# CTR_MCU_Power.net
KiCad netlist of a schematic drawn in Altium Designer
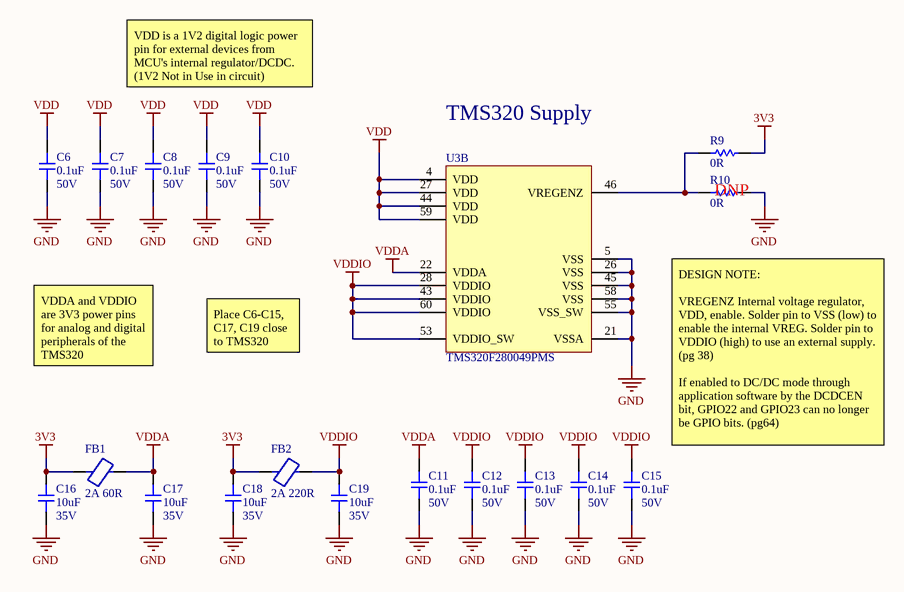
[diagram p0: CTR_MCU_Power.SchDoc]

(export (version "E")
  (design (tool "Eeschema 10.0.6"))
  (components
    (comp (ref "C6")
      (value "0603-0.1uF-50V")
      (footprint "CAP-0603")
      (description "CAP CER 0.1UF 50V X7R 0603")
      (fields
        (field (name "MANUFACTURER") "Kyocera AVX")
        (field (name "MANUFACTURER PART NUMBER") "06035C104JAT4A")
        (field (name "CAPACITANCE") "0.1uF")
        (field (name "VOLTAGE RATING") "50V")
      )
      (libsource (lib "InverterSCHLib") (part "0603-0.1uF-50V"))
    )
    (comp (ref "C7")
      (value "0603-0.1uF-50V")
      (footprint "CAP-0603")
      (description "CAP CER 0.1UF 50V X7R 0603")
      (fields
        (field (name "MANUFACTURER") "Kyocera AVX")
        (field (name "MANUFACTURER PART NUMBER") "06035C104JAT4A")
        (field (name "CAPACITANCE") "0.1uF")
        (field (name "VOLTAGE RATING") "50V")
      )
      (libsource (lib "InverterSCHLib") (part "0603-0.1uF-50V"))
    )
    (comp (ref "C8")
      (value "0603-0.1uF-50V")
      (footprint "CAP-0603")
      (description "CAP CER 0.1UF 50V X7R 0603")
      (fields
        (field (name "MANUFACTURER") "Kyocera AVX")
        (field (name "MANUFACTURER PART NUMBER") "06035C104JAT4A")
        (field (name "CAPACITANCE") "0.1uF")
        (field (name "VOLTAGE RATING") "50V")
      )
      (libsource (lib "InverterSCHLib") (part "0603-0.1uF-50V"))
    )
    (comp (ref "C9")
      (value "0603-0.1uF-50V")
      (footprint "CAP-0603")
      (description "CAP CER 0.1UF 50V X7R 0603")
      (fields
        (field (name "MANUFACTURER") "Kyocera AVX")
        (field (name "MANUFACTURER PART NUMBER") "06035C104JAT4A")
        (field (name "CAPACITANCE") "0.1uF")
        (field (name "VOLTAGE RATING") "50V")
      )
      (libsource (lib "InverterSCHLib") (part "0603-0.1uF-50V"))
    )
    (comp (ref "C10")
      (value "0603-0.1uF-50V")
      (footprint "CAP-0603")
      (description "CAP CER 0.1UF 50V X7R 0603")
      (fields
        (field (name "MANUFACTURER") "Kyocera AVX")
        (field (name "MANUFACTURER PART NUMBER") "06035C104JAT4A")
        (field (name "CAPACITANCE") "0.1uF")
        (field (name "VOLTAGE RATING") "50V")
      )
      (libsource (lib "InverterSCHLib") (part "0603-0.1uF-50V"))
    )
    (comp (ref "C11")
      (value "0603-0.1uF-50V")
      (footprint "CAP-0603")
      (description "CAP CER 0.1UF 50V X7R 0603")
      (fields
        (field (name "MANUFACTURER") "Kyocera AVX")
        (field (name "MANUFACTURER PART NUMBER") "06035C104JAT4A")
        (field (name "CAPACITANCE") "0.1uF")
        (field (name "VOLTAGE RATING") "50V")
      )
      (libsource (lib "InverterSCHLib") (part "0603-0.1uF-50V"))
    )
    (comp (ref "C12")
      (value "0603-0.1uF-50V")
      (footprint "CAP-0603")
      (description "CAP CER 0.1UF 50V X7R 0603")
      (fields
        (field (name "MANUFACTURER") "Kyocera AVX")
        (field (name "MANUFACTURER PART NUMBER") "06035C104JAT4A")
        (field (name "CAPACITANCE") "0.1uF")
        (field (name "VOLTAGE RATING") "50V")
      )
      (libsource (lib "InverterSCHLib") (part "0603-0.1uF-50V"))
    )
    (comp (ref "C13")
      (value "0603-0.1uF-50V")
      (footprint "CAP-0603")
      (description "CAP CER 0.1UF 50V X7R 0603")
      (fields
        (field (name "MANUFACTURER") "Kyocera AVX")
        (field (name "MANUFACTURER PART NUMBER") "06035C104JAT4A")
        (field (name "CAPACITANCE") "0.1uF")
        (field (name "VOLTAGE RATING") "50V")
      )
      (libsource (lib "InverterSCHLib") (part "0603-0.1uF-50V"))
    )
    (comp (ref "C14")
      (value "0603-0.1uF-50V")
      (footprint "CAP-0603")
      (description "CAP CER 0.1UF 50V X7R 0603")
      (fields
        (field (name "MANUFACTURER") "Kyocera AVX")
        (field (name "MANUFACTURER PART NUMBER") "06035C104JAT4A")
        (field (name "CAPACITANCE") "0.1uF")
        (field (name "VOLTAGE RATING") "50V")
      )
      (libsource (lib "InverterSCHLib") (part "0603-0.1uF-50V"))
    )
    (comp (ref "C15")
      (value "0603-0.1uF-50V")
      (footprint "CAP-0603")
      (description "CAP CER 0.1UF 50V X7R 0603")
      (fields
        (field (name "MANUFACTURER") "Kyocera AVX")
        (field (name "MANUFACTURER PART NUMBER") "06035C104JAT4A")
        (field (name "CAPACITANCE") "0.1uF")
        (field (name "VOLTAGE RATING") "50V")
      )
      (libsource (lib "InverterSCHLib") (part "0603-0.1uF-50V"))
    )
    (comp (ref "C16")
      (value "0603-10uF-35V")
      (footprint "CAP-0603")
      (description "CAP CER 10UF 35V X5R 0603")
      (fields
        (field (name "MANUFACTURER") "Murata")
        (field (name "MANUFACTURER PART NUMBER") "GRM188R6YA106MA73D")
        (field (name "CAPACITANCE") "10uF")
        (field (name "VOLTAGE RATING") "35V")
      )
      (libsource (lib "InverterSCHLib") (part "0603-10uF-35V"))
    )
    (comp (ref "C17")
      (value "0603-10uF-35V")
      (footprint "CAP-0603")
      (description "CAP CER 10UF 35V X5R 0603")
      (fields
        (field (name "MANUFACTURER") "Murata")
        (field (name "MANUFACTURER PART NUMBER") "GRM188R6YA106MA73D")
        (field (name "CAPACITANCE") "10uF")
        (field (name "VOLTAGE RATING") "35V")
      )
      (libsource (lib "InverterSCHLib") (part "0603-10uF-35V"))
    )
    (comp (ref "C18")
      (value "0603-10uF-35V")
      (footprint "CAP-0603")
      (description "CAP CER 10UF 35V X5R 0603")
      (fields
        (field (name "MANUFACTURER") "Murata")
        (field (name "MANUFACTURER PART NUMBER") "GRM188R6YA106MA73D")
        (field (name "CAPACITANCE") "10uF")
        (field (name "VOLTAGE RATING") "35V")
      )
      (libsource (lib "InverterSCHLib") (part "0603-10uF-35V"))
    )
    (comp (ref "C19")
      (value "0603-10uF-35V")
      (footprint "CAP-0603")
      (description "CAP CER 10UF 35V X5R 0603")
      (fields
        (field (name "MANUFACTURER") "Murata")
        (field (name "MANUFACTURER PART NUMBER") "GRM188R6YA106MA73D")
        (field (name "CAPACITANCE") "10uF")
        (field (name "VOLTAGE RATING") "35V")
      )
      (libsource (lib "InverterSCHLib") (part "0603-10uF-35V"))
    )
    (comp (ref "FB1")
      (value "2A 60R")
      (footprint "FB-0805")
      (description "FERRITE BEAD 60 OHM 0805 1LN")
      (fields
        (field (name "MANUFACTURER") "Taiyo Yuden")
        (field (name "MANUFACTURER PART NUMBER") "BKP2125HS600-T")
      )
      (libsource (lib "InverterSCHLib") (part "BKP2125HS600-T"))
    )
    (comp (ref "FB2")
      (value "2A 220R")
      (footprint "FB-0805")
      (description "FERRITE BEAD 220 OHM 0805 1LN")
      (fields
        (field (name "MANUFACTURER") "Murata")
        (field (name "MANUFACTURER PART NUMBER") "BLM21PG221SN1D")
      )
      (libsource (lib "InverterSCHLib") (part "BLM21PG221SN1D"))
    )
    (comp (ref "R9")
      (value "0R")
      (footprint "RES-0603")
      (description "RES SMD 0 OHM JUMPER 1/10W 0603")
      (fields
        (field (name "MANUFACTURER") "Yageo")
        (field (name "MANUFACTURER PART NUMBER") "RC0603JR-070RL")
      )
      (libsource (lib "InverterSCHLib") (part "0603-0R"))
    )
    (comp (ref "R10")
      (value "0R")
      (footprint "RES-0603")
      (description "RES SMD 0 OHM JUMPER 1/10W 0603")
      (fields
        (field (name "MANUFACTURER") "Yageo")
        (field (name "MANUFACTURER PART NUMBER") "RC0603JR-070RL")
      )
      (libsource (lib "InverterSCHLib") (part "0603-0R"))
    )
    (comp (ref "U3")
      (value "TMS320F280049PMS")
      (footprint "64QFP")
      (description "IC MCU 32BIT 256KB FLASH 64LQFP")
      (fields
        (field (name "MANUFACTURER") "Texas Instruments")
        (field (name "MANUFACTURER PART NUMBER") "F280049CPMS")
      )
      (libsource (lib "InverterSCHLib") (part "TMS320F280049"))
    )
  )
  (nets
    (net (code "1") (name "3V3") (class "Default")
      (node (ref "C16") (pin "2") (pinfunction "2_2") (pintype "passive"))
      (node (ref "C18") (pin "2") (pinfunction "2_2") (pintype "passive"))
      (node (ref "FB1") (pin "1") (pinfunction "1_1") (pintype "passive"))
      (node (ref "FB2") (pin "1") (pinfunction "1_1") (pintype "passive"))
      (node (ref "R9") (pin "2") (pinfunction "2_2") (pintype "passive"))
    )
    (net (code "2") (name "GND") (class "Default")
      (node (ref "C10") (pin "1") (pinfunction "1_1") (pintype "passive"))
      (node (ref "C11") (pin "1") (pinfunction "1_1") (pintype "passive"))
      (node (ref "C12") (pin "1") (pinfunction "1_1") (pintype "passive"))
      (node (ref "C13") (pin "1") (pinfunction "1_1") (pintype "passive"))
      (node (ref "C14") (pin "1") (pinfunction "1_1") (pintype "passive"))
      (node (ref "C15") (pin "1") (pinfunction "1_1") (pintype "passive"))
      (node (ref "C16") (pin "1") (pinfunction "1_1") (pintype "passive"))
      (node (ref "C17") (pin "1") (pinfunction "1_1") (pintype "passive"))
      (node (ref "C18") (pin "1") (pinfunction "1_1") (pintype "passive"))
      (node (ref "C19") (pin "1") (pinfunction "1_1") (pintype "passive"))
      (node (ref "C6") (pin "1") (pinfunction "1_1") (pintype "passive"))
      (node (ref "C7") (pin "1") (pinfunction "1_1") (pintype "passive"))
      (node (ref "C8") (pin "1") (pinfunction "1_1") (pintype "passive"))
      (node (ref "C9") (pin "1") (pinfunction "1_1") (pintype "passive"))
      (node (ref "R10") (pin "2") (pinfunction "2_2") (pintype "passive"))
      (node (ref "U3") (pin "21") (pinfunction "VSSA_21") (pintype "passive"))
      (node (ref "U3") (pin "26") (pinfunction "VSS_26") (pintype "passive"))
      (node (ref "U3") (pin "45") (pinfunction "VSS_45") (pintype "passive"))
      (node (ref "U3") (pin "5") (pinfunction "VSS_5") (pintype "passive"))
      (node (ref "U3") (pin "55") (pinfunction "VSS_SW_55") (pintype "passive"))
      (node (ref "U3") (pin "58") (pinfunction "VSS_58") (pintype "passive"))
    )
    (net (code "3") (name "Net-(U3B-VREGENZ)") (class "Default")
      (node (ref "R10") (pin "1") (pinfunction "1_1") (pintype "passive"))
      (node (ref "R9") (pin "1") (pinfunction "1_1") (pintype "passive"))
      (node (ref "U3") (pin "46") (pinfunction "VREGENZ_46") (pintype "passive"))
    )
    (net (code "4") (name "VDD") (class "Default")
      (node (ref "C10") (pin "2") (pinfunction "2_2") (pintype "passive"))
      (node (ref "C6") (pin "2") (pinfunction "2_2") (pintype "passive"))
      (node (ref "C7") (pin "2") (pinfunction "2_2") (pintype "passive"))
      (node (ref "C8") (pin "2") (pinfunction "2_2") (pintype "passive"))
      (node (ref "C9") (pin "2") (pinfunction "2_2") (pintype "passive"))
      (node (ref "U3") (pin "27") (pinfunction "VDD_27") (pintype "passive"))
      (node (ref "U3") (pin "4") (pinfunction "VDD_4") (pintype "passive"))
      (node (ref "U3") (pin "44") (pinfunction "VDD_44") (pintype "passive"))
      (node (ref "U3") (pin "59") (pinfunction "VDD_59") (pintype "passive"))
    )
    (net (code "5") (name "VDDA") (class "Default")
      (node (ref "C11") (pin "2") (pinfunction "2_2") (pintype "passive"))
      (node (ref "C17") (pin "2") (pinfunction "2_2") (pintype "passive"))
      (node (ref "FB1") (pin "2") (pinfunction "2_2") (pintype "passive"))
      (node (ref "U3") (pin "22") (pinfunction "VDDA_22") (pintype "passive"))
    )
    (net (code "6") (name "VDDIO") (class "Default")
      (node (ref "C12") (pin "2") (pinfunction "2_2") (pintype "passive"))
      (node (ref "C13") (pin "2") (pinfunction "2_2") (pintype "passive"))
      (node (ref "C14") (pin "2") (pinfunction "2_2") (pintype "passive"))
      (node (ref "C15") (pin "2") (pinfunction "2_2") (pintype "passive"))
      (node (ref "C19") (pin "2") (pinfunction "2_2") (pintype "passive"))
      (node (ref "FB2") (pin "2") (pinfunction "2_2") (pintype "passive"))
      (node (ref "U3") (pin "28") (pinfunction "VDDIO_28") (pintype "passive"))
      (node (ref "U3") (pin "43") (pinfunction "VDDIO_43") (pintype "passive"))
      (node (ref "U3") (pin "53") (pinfunction "VDDIO_SW_53") (pintype "passive"))
      (node (ref "U3") (pin "60") (pinfunction "VDDIO_60") (pintype "passive"))
    )
  )
)
